# 24dc_cup_wash_sucction.net
KiCad netlist of a schematic drawn in EAGLE
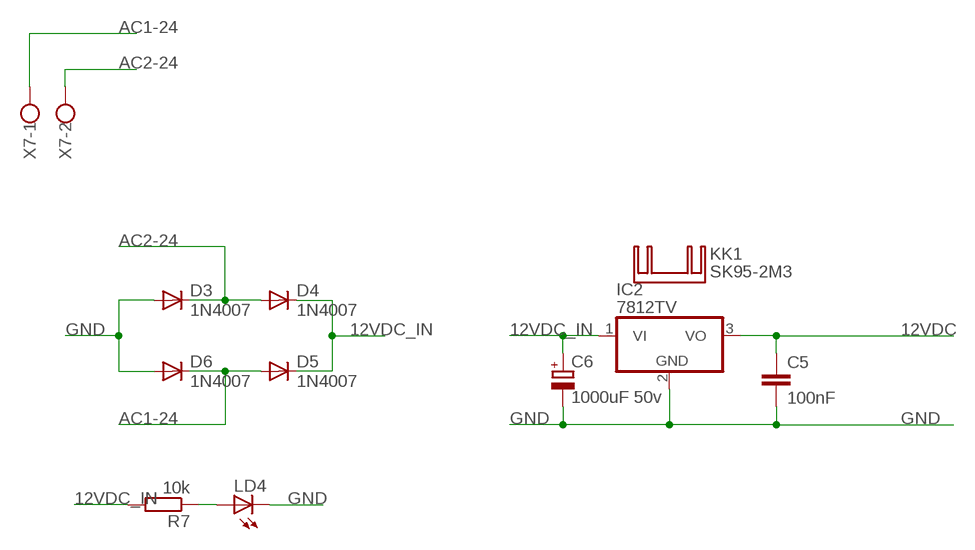
[diagram p0: schematic, sheet 1]
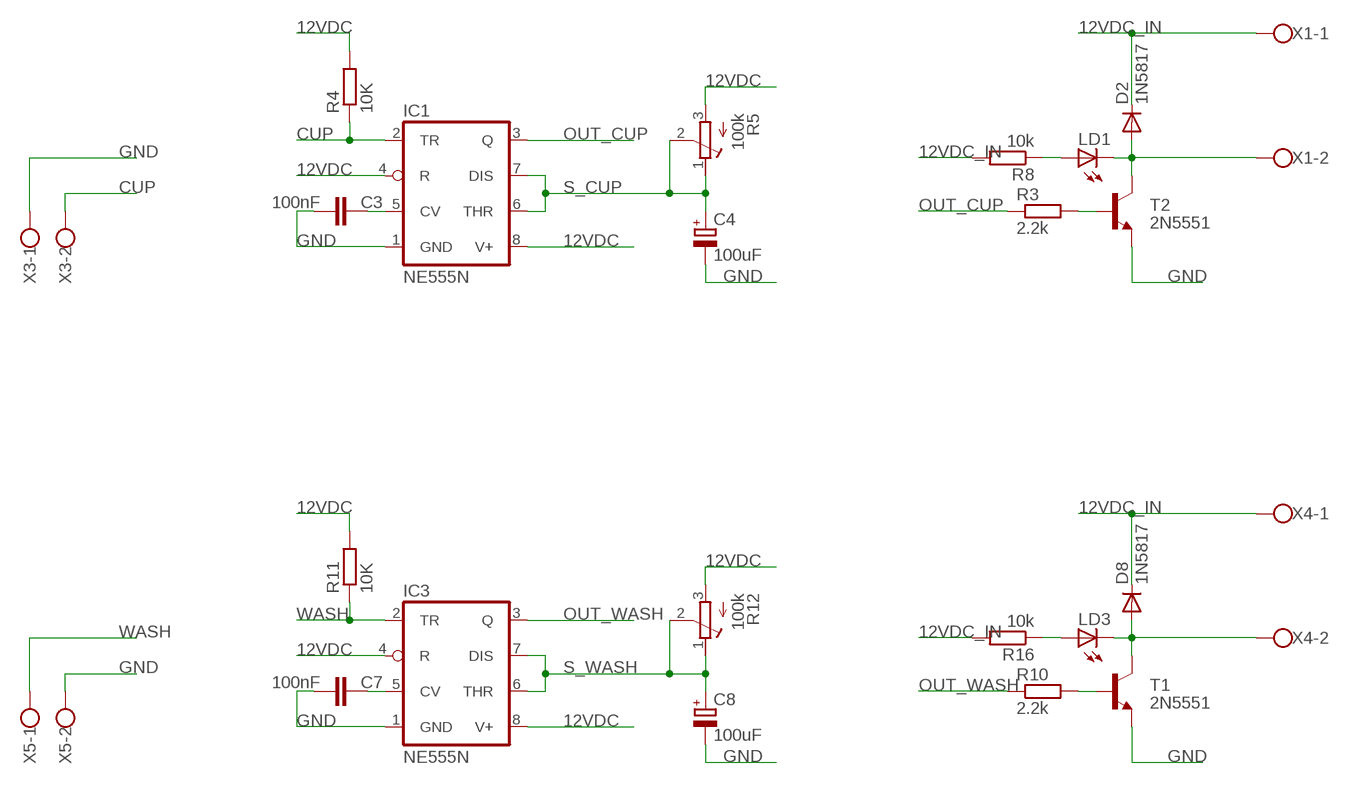
[diagram p1: schematic, sheet 2]
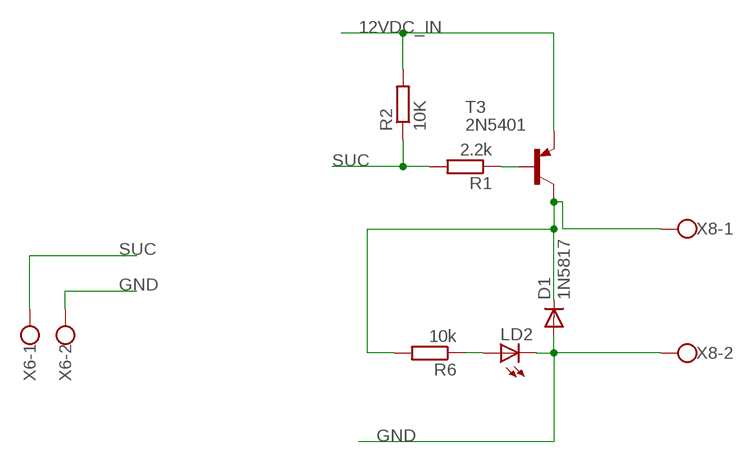
[diagram p2: schematic, sheet 3]

(export (version "E")
  (design (tool "Eeschema 10.0.6"))
  (components
    (comp (ref "D1")
      (value "1N5817")
      (footprint "eagle-import:DO41-10")
      (libsource (lib "eagle-import") (part "1N4004"))
    )
    (comp (ref "LD2")
      (value "LED5MM")
      (footprint "eagle-import:LED5MM")
      (libsource (lib "eagle-import") (part "LED5MM"))
    )
    (comp (ref "R1")
      (value "2.2k")
      (footprint "eagle-import:0207_10")
      (libsource (lib "eagle-import") (part "R-EU_0207/10"))
    )
    (comp (ref "R2")
      (value "10K")
      (footprint "eagle-import:0207_10")
      (libsource (lib "eagle-import") (part "R-EU_0207/10"))
    )
    (comp (ref "R6")
      (value "10k")
      (footprint "eagle-import:0207_10")
      (libsource (lib "eagle-import") (part "R-EU_0207/10"))
    )
    (comp (ref "T3")
      (value "2N5401")
      (footprint "eagle-import:TO92-EBC")
      (libsource (lib "eagle-import") (part "-PNP-TO92-EBC2N5401"))
    )
    (comp (ref "X6")
      (value "W237-102")
      (footprint "eagle-import:W237-102")
      (libsource (lib "eagle-import") (part "W237-102"))
    )
    (comp (ref "X8")
      (value "W237-102")
      (footprint "eagle-import:W237-102")
      (libsource (lib "eagle-import") (part "W237-102"))
    )
    (comp (ref "C3")
      (value "100nF")
      (footprint "eagle-import:C050-025X075")
      (libsource (lib "eagle-import") (part "C-EU050-025X075"))
    )
    (comp (ref "C4")
      (value "100uF")
      (footprint "eagle-import:E3,5-8")
      (libsource (lib "eagle-import") (part "CPOL-EUE3.5-8"))
    )
    (comp (ref "C7")
      (value "100nF")
      (footprint "eagle-import:C050-025X075")
      (libsource (lib "eagle-import") (part "C-EU050-025X075"))
    )
    (comp (ref "C8")
      (value "100uF")
      (footprint "eagle-import:E3,5-8")
      (libsource (lib "eagle-import") (part "CPOL-EUE3.5-8"))
    )
    (comp (ref "D2")
      (value "1N5817")
      (footprint "eagle-import:DO41-10")
      (libsource (lib "eagle-import") (part "1N4004"))
    )
    (comp (ref "D8")
      (value "1N5817")
      (footprint "eagle-import:DO41-10")
      (libsource (lib "eagle-import") (part "1N4004"))
    )
    (comp (ref "IC1")
      (value "NE555N")
      (footprint "eagle-import:DIL08-ROUND")
      (libsource (lib "eagle-import") (part "555NNE"))
    )
    (comp (ref "IC3")
      (value "NE555N")
      (footprint "eagle-import:DIL08-ROUND")
      (libsource (lib "eagle-import") (part "555NNE"))
    )
    (comp (ref "LD1")
      (value "LED5MM")
      (footprint "eagle-import:LED5MM")
      (libsource (lib "eagle-import") (part "LED5MM"))
    )
    (comp (ref "LD3")
      (value "LED5MM")
      (footprint "eagle-import:LED5MM")
      (libsource (lib "eagle-import") (part "LED5MM"))
    )
    (comp (ref "R3")
      (value "2.2k")
      (footprint "eagle-import:0207_10")
      (libsource (lib "eagle-import") (part "R-EU_0207/10"))
    )
    (comp (ref "R4")
      (value "10K")
      (footprint "eagle-import:0207_10")
      (libsource (lib "eagle-import") (part "R-EU_0207/10"))
    )
    (comp (ref "R5")
      (value "100k")
      (footprint "eagle-import:RTRIMT93XA")
      (libsource (lib "eagle-import") (part "R-TRIMMT93XA"))
    )
    (comp (ref "R8")
      (value "10k")
      (footprint "eagle-import:0207_10")
      (libsource (lib "eagle-import") (part "R-EU_0207/10"))
    )
    (comp (ref "R10")
      (value "2.2k")
      (footprint "eagle-import:0207_10")
      (libsource (lib "eagle-import") (part "R-EU_0207/10"))
    )
    (comp (ref "R11")
      (value "10K")
      (footprint "eagle-import:0207_10")
      (libsource (lib "eagle-import") (part "R-EU_0207/10"))
    )
    (comp (ref "R12")
      (value "100k")
      (footprint "eagle-import:RTRIMT93XA")
      (libsource (lib "eagle-import") (part "R-TRIMMT93XA"))
    )
    (comp (ref "R16")
      (value "10k")
      (footprint "eagle-import:0207_10")
      (libsource (lib "eagle-import") (part "R-EU_0207/10"))
    )
    (comp (ref "T1")
      (value "2N5551")
      (footprint "eagle-import:TO92-EBC-OVAL")
      (libsource (lib "eagle-import") (part "2N2222"))
    )
    (comp (ref "T2")
      (value "2N5551")
      (footprint "eagle-import:TO92-EBC-OVAL")
      (libsource (lib "eagle-import") (part "2N2222"))
    )
    (comp (ref "X1")
      (value "W237-102")
      (footprint "eagle-import:W237-102")
      (libsource (lib "eagle-import") (part "W237-102"))
    )
    (comp (ref "X3")
      (value "W237-102")
      (footprint "eagle-import:W237-102")
      (libsource (lib "eagle-import") (part "W237-102"))
    )
    (comp (ref "X4")
      (value "W237-102")
      (footprint "eagle-import:W237-102")
      (libsource (lib "eagle-import") (part "W237-102"))
    )
    (comp (ref "X5")
      (value "W237-102")
      (footprint "eagle-import:W237-102")
      (libsource (lib "eagle-import") (part "W237-102"))
    )
    (comp (ref "C5")
      (value "100nF")
      (footprint "eagle-import:C050-025X075")
      (libsource (lib "eagle-import") (part "C-EU050-025X075"))
    )
    (comp (ref "C6")
      (value "1000uF 50v")
      (footprint "eagle-import:E5-13")
      (libsource (lib "eagle-import") (part "CPOL-EUE5-13"))
    )
    (comp (ref "D3")
      (value "1N4007")
      (footprint "eagle-import:DO41-10")
      (libsource (lib "eagle-import") (part "adafruit_420_1N4004"))
    )
    (comp (ref "D4")
      (value "1N4007")
      (footprint "eagle-import:DO41-10")
      (libsource (lib "eagle-import") (part "adafruit_420_1N4004"))
    )
    (comp (ref "D5")
      (value "1N4007")
      (footprint "eagle-import:DO41-10")
      (libsource (lib "eagle-import") (part "adafruit_420_1N4004"))
    )
    (comp (ref "D6")
      (value "1N4007")
      (footprint "eagle-import:DO41-10")
      (libsource (lib "eagle-import") (part "adafruit_420_1N4004"))
    )
    (comp (ref "IC2")
      (value "7812TV")
      (footprint "eagle-import:TO220V")
      (libsource (lib "eagle-import") (part "78TV12"))
    )
    (comp (ref "KK1")
      (value "SK95-2M3")
      (footprint "eagle-import:SK95-2M3")
      (libsource (lib "eagle-import") (part "SK95-2M3"))
    )
    (comp (ref "LD4")
      (value "LED5MM")
      (footprint "eagle-import:LED5MM")
      (libsource (lib "eagle-import") (part "LED5MM"))
    )
    (comp (ref "R7")
      (value "10k")
      (footprint "eagle-import:0207_10")
      (libsource (lib "eagle-import") (part "R-EU_0207/10"))
    )
    (comp (ref "X7")
      (value "W237-102")
      (footprint "eagle-import:W237-102")
      (libsource (lib "eagle-import") (part "W237-102"))
    )
  )
  (nets
    (net (code "1") (name "12VDC") (class "Default")
      (node (ref "C5") (pin "1") (pinfunction "1_1") (pintype "passive"))
      (node (ref "IC1") (pin "4") (pinfunction "R_4") (pintype "input"))
      (node (ref "IC1") (pin "8") (pinfunction "V+_8") (pintype "power_in"))
      (node (ref "IC2") (pin "3") (pinfunction "VO_3") (pintype "passive"))
      (node (ref "IC3") (pin "4") (pinfunction "R_4") (pintype "input"))
      (node (ref "IC3") (pin "8") (pinfunction "V+_8") (pintype "power_in"))
      (node (ref "R11") (pin "2") (pinfunction "2_2") (pintype "passive"))
      (node (ref "R12") (pin "3") (pinfunction "A_3") (pintype "passive"))
      (node (ref "R4") (pin "2") (pinfunction "2_2") (pintype "passive"))
      (node (ref "R5") (pin "3") (pinfunction "A_3") (pintype "passive"))
    )
    (net (code "2") (name "12VDC_IN") (class "Default")
      (node (ref "C6") (pin "+") (pinfunction "+_+") (pintype "passive"))
      (node (ref "D2") (pin "C") (pinfunction "C_C") (pintype "passive"))
      (node (ref "D4") (pin "C") (pinfunction "C_C") (pintype "passive"))
      (node (ref "D5") (pin "C") (pinfunction "C_C") (pintype "passive"))
      (node (ref "D8") (pin "C") (pinfunction "C_C") (pintype "passive"))
      (node (ref "IC2") (pin "1") (pinfunction "VI_1") (pintype "input"))
      (node (ref "R16") (pin "2") (pinfunction "2_2") (pintype "passive"))
      (node (ref "R2") (pin "2") (pinfunction "2_2") (pintype "passive"))
      (node (ref "R7") (pin "2") (pinfunction "2_2") (pintype "passive"))
      (node (ref "R8") (pin "2") (pinfunction "2_2") (pintype "passive"))
      (node (ref "T3") (pin "E") (pinfunction "E_E") (pintype "passive"))
      (node (ref "X1") (pin "1") (pinfunction "KL_1") (pintype "passive"))
      (node (ref "X4") (pin "1") (pinfunction "KL_1") (pintype "passive"))
    )
    (net (code "3") (name "AC1-24") (class "Default")
      (node (ref "D5") (pin "A") (pinfunction "A_A") (pintype "passive"))
      (node (ref "D6") (pin "C") (pinfunction "C_C") (pintype "passive"))
      (node (ref "X7") (pin "1") (pinfunction "KL_1") (pintype "passive"))
    )
    (net (code "4") (name "AC2-24") (class "Default")
      (node (ref "D3") (pin "C") (pinfunction "C_C") (pintype "passive"))
      (node (ref "D4") (pin "A") (pinfunction "A_A") (pintype "passive"))
      (node (ref "X7") (pin "2") (pinfunction "KL_2") (pintype "passive"))
    )
    (net (code "5") (name "CUP") (class "Default")
      (node (ref "IC1") (pin "2") (pinfunction "TR_2") (pintype "input"))
      (node (ref "R4") (pin "1") (pinfunction "1_1") (pintype "passive"))
      (node (ref "X3") (pin "2") (pinfunction "KL_2") (pintype "passive"))
    )
    (net (code "6") (name "GND") (class "Default")
      (node (ref "C3") (pin "2") (pinfunction "2_2") (pintype "passive"))
      (node (ref "C4") (pin "-") (pinfunction "-_-") (pintype "passive"))
      (node (ref "C5") (pin "2") (pinfunction "2_2") (pintype "passive"))
      (node (ref "C6") (pin "-") (pinfunction "-_-") (pintype "passive"))
      (node (ref "C7") (pin "2") (pinfunction "2_2") (pintype "passive"))
      (node (ref "C8") (pin "-") (pinfunction "-_-") (pintype "passive"))
      (node (ref "D1") (pin "A") (pinfunction "A_A") (pintype "passive"))
      (node (ref "D3") (pin "A") (pinfunction "A_A") (pintype "passive"))
      (node (ref "D6") (pin "A") (pinfunction "A_A") (pintype "passive"))
      (node (ref "IC1") (pin "1") (pinfunction "GND_1") (pintype "power_in"))
      (node (ref "IC2") (pin "2") (pinfunction "GND_2") (pintype "passive"))
      (node (ref "IC3") (pin "1") (pinfunction "GND_1") (pintype "power_in"))
      (node (ref "LD2") (pin "K") (pinfunction "C_K") (pintype "passive"))
      (node (ref "LD4") (pin "K") (pinfunction "C_K") (pintype "passive"))
      (node (ref "T1") (pin "E") (pinfunction "E_E") (pintype "passive"))
      (node (ref "T2") (pin "E") (pinfunction "E_E") (pintype "passive"))
      (node (ref "X3") (pin "1") (pinfunction "KL_1") (pintype "passive"))
      (node (ref "X5") (pin "2") (pinfunction "KL_2") (pintype "passive"))
      (node (ref "X6") (pin "2") (pinfunction "KL_2") (pintype "passive"))
      (node (ref "X8") (pin "2") (pinfunction "KL_2") (pintype "passive"))
    )
    (net (code "7") (name "Net-(IC1-CV)") (class "Default")
      (node (ref "C3") (pin "1") (pinfunction "1_1") (pintype "passive"))
      (node (ref "IC1") (pin "5") (pinfunction "CV_5") (pintype "input"))
    )
    (net (code "8") (name "Net-(IC3-CV)") (class "Default")
      (node (ref "C7") (pin "1") (pinfunction "1_1") (pintype "passive"))
      (node (ref "IC3") (pin "5") (pinfunction "CV_5") (pintype "input"))
    )
    (net (code "9") (name "Net-(LD1-C)") (class "Default")
      (node (ref "D2") (pin "A") (pinfunction "A_A") (pintype "passive"))
      (node (ref "LD1") (pin "K") (pinfunction "C_K") (pintype "passive"))
      (node (ref "T2") (pin "C") (pinfunction "C_C") (pintype "passive"))
      (node (ref "X1") (pin "2") (pinfunction "KL_2") (pintype "passive"))
    )
    (net (code "10") (name "Net-(LD1-PadA)") (class "Default")
      (node (ref "LD1") (pin "A") (pinfunction "A_A") (pintype "passive"))
      (node (ref "R8") (pin "1") (pinfunction "1_1") (pintype "passive"))
    )
    (net (code "11") (name "Net-(LD2-PadA)") (class "Default")
      (node (ref "LD2") (pin "A") (pinfunction "A_A") (pintype "passive"))
      (node (ref "R6") (pin "1") (pinfunction "1_1") (pintype "passive"))
    )
    (net (code "12") (name "Net-(LD3-C)") (class "Default")
      (node (ref "D8") (pin "A") (pinfunction "A_A") (pintype "passive"))
      (node (ref "LD3") (pin "K") (pinfunction "C_K") (pintype "passive"))
      (node (ref "T1") (pin "C") (pinfunction "C_C") (pintype "passive"))
      (node (ref "X4") (pin "2") (pinfunction "KL_2") (pintype "passive"))
    )
    (net (code "13") (name "Net-(LD3-PadA)") (class "Default")
      (node (ref "LD3") (pin "A") (pinfunction "A_A") (pintype "passive"))
      (node (ref "R16") (pin "1") (pinfunction "1_1") (pintype "passive"))
    )
    (net (code "14") (name "Net-(LD4-PadA)") (class "Default")
      (node (ref "LD4") (pin "A") (pinfunction "A_A") (pintype "passive"))
      (node (ref "R7") (pin "1") (pinfunction "1_1") (pintype "passive"))
    )
    (net (code "15") (name "Net-(R1-Pad1)") (class "Default")
      (node (ref "R1") (pin "1") (pinfunction "1_1") (pintype "passive"))
      (node (ref "T3") (pin "B") (pinfunction "B_B") (pintype "passive"))
    )
    (net (code "16") (name "Net-(R3-Pad2)") (class "Default")
      (node (ref "R3") (pin "2") (pinfunction "2_2") (pintype "passive"))
      (node (ref "T2") (pin "B") (pinfunction "B_B") (pintype "passive"))
    )
    (net (code "17") (name "Net-(R10-Pad2)") (class "Default")
      (node (ref "R10") (pin "2") (pinfunction "2_2") (pintype "passive"))
      (node (ref "T1") (pin "B") (pinfunction "B_B") (pintype "passive"))
    )
    (net (code "18") (name "Net-(X8A-KL)") (class "Default")
      (node (ref "D1") (pin "C") (pinfunction "C_C") (pintype "passive"))
      (node (ref "R6") (pin "2") (pinfunction "2_2") (pintype "passive"))
      (node (ref "T3") (pin "C") (pinfunction "C_C") (pintype "passive"))
      (node (ref "X8") (pin "1") (pinfunction "KL_1") (pintype "passive"))
    )
    (net (code "19") (name "OUT_CUP") (class "Default")
      (node (ref "IC1") (pin "3") (pinfunction "Q_3") (pintype "output"))
      (node (ref "R3") (pin "1") (pinfunction "1_1") (pintype "passive"))
    )
    (net (code "20") (name "OUT_WASH") (class "Default")
      (node (ref "IC3") (pin "3") (pinfunction "Q_3") (pintype "output"))
      (node (ref "R10") (pin "1") (pinfunction "1_1") (pintype "passive"))
    )
    (net (code "21") (name "SUC") (class "Default")
      (node (ref "R1") (pin "2") (pinfunction "2_2") (pintype "passive"))
      (node (ref "R2") (pin "1") (pinfunction "1_1") (pintype "passive"))
      (node (ref "X6") (pin "1") (pinfunction "KL_1") (pintype "passive"))
    )
    (net (code "22") (name "S_CUP") (class "Default")
      (node (ref "C4") (pin "+") (pinfunction "+_+") (pintype "passive"))
      (node (ref "IC1") (pin "6") (pinfunction "THR_6") (pintype "input"))
      (node (ref "IC1") (pin "7") (pinfunction "DIS_7") (pintype "input"))
      (node (ref "R5") (pin "1") (pinfunction "E_1") (pintype "passive"))
      (node (ref "R5") (pin "2") (pinfunction "S_2") (pintype "passive"))
    )
    (net (code "23") (name "S_WASH") (class "Default")
      (node (ref "C8") (pin "+") (pinfunction "+_+") (pintype "passive"))
      (node (ref "IC3") (pin "6") (pinfunction "THR_6") (pintype "input"))
      (node (ref "IC3") (pin "7") (pinfunction "DIS_7") (pintype "input"))
      (node (ref "R12") (pin "1") (pinfunction "E_1") (pintype "passive"))
      (node (ref "R12") (pin "2") (pinfunction "S_2") (pintype "passive"))
    )
    (net (code "24") (name "WASH") (class "Default")
      (node (ref "IC3") (pin "2") (pinfunction "TR_2") (pintype "input"))
      (node (ref "R11") (pin "1") (pinfunction "1_1") (pintype "passive"))
      (node (ref "X5") (pin "1") (pinfunction "KL_1") (pintype "passive"))
    )
  )
)
